# Badge_03v2-prog-2layer.net
KiCad netlist of a schematic drawn in EAGLE
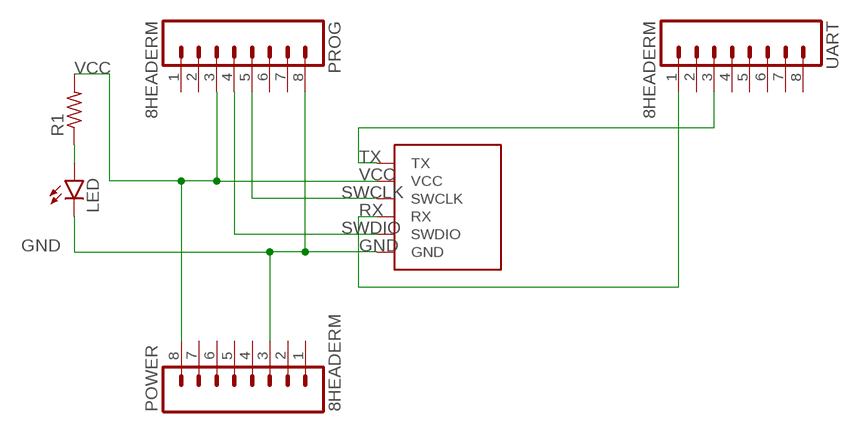
[diagram p0: schematic, sheet 1]

(export (version "E")
  (design (tool "Eeschema 10.0.6"))
  (components
    (comp (ref "J1")
      (value "PROG_CONN_6")
      (footprint "eagle-import:TH_CONN_6")
      (libsource (lib "eagle-import") (part "PROG_CONN_6"))
    )
    (comp (ref "LED")
      (value "LED")
      (footprint "eagle-import:LED-0603")
      (libsource (lib "eagle-import") (part "LED"))
    )
    (comp (ref "POWER")
      (value "8HEADERM")
      (footprint "eagle-import:1X08_ROUND")
      (libsource (lib "eagle-import") (part "8HEADERM"))
    )
    (comp (ref "PROG")
      (value "8HEADERM")
      (footprint "eagle-import:1X08_ROUND")
      (libsource (lib "eagle-import") (part "8HEADERM"))
    )
    (comp (ref "R1")
      (value "R-US_R0603")
      (footprint "eagle-import:R0603")
      (libsource (lib "eagle-import") (part "R-US_R0603"))
    )
    (comp (ref "UART")
      (value "8HEADERM")
      (footprint "eagle-import:1X08_ROUND")
      (libsource (lib "eagle-import") (part "8HEADERM"))
    )
  )
  (nets
    (net (code "1") (name "/GND") (class "Default")
      (node (ref "J1") (pin "GND") (pinfunction "GND_GND") (pintype "bidirectional"))
      (node (ref "LED") (pin "C") (pinfunction "C_C") (pintype "passive"))
      (node (ref "POWER") (pin "3") (pinfunction "3_3") (pintype "passive"))
      (node (ref "PROG") (pin "8") (pinfunction "8_8") (pintype "passive"))
    )
    (net (code "2") (name "/RX") (class "Default")
      (node (ref "J1") (pin "RX") (pinfunction "RX_RX") (pintype "bidirectional"))
      (node (ref "UART") (pin "1") (pinfunction "1_1") (pintype "passive"))
    )
    (net (code "3") (name "/SWCLK") (class "Default")
      (node (ref "J1") (pin "SWCLK") (pinfunction "SWCLK_SWCLK") (pintype "bidirectional"))
      (node (ref "PROG") (pin "5") (pinfunction "5_5") (pintype "passive"))
    )
    (net (code "4") (name "/SWDIO") (class "Default")
      (node (ref "J1") (pin "SWDIO") (pinfunction "SWDIO_SWDIO") (pintype "bidirectional"))
      (node (ref "PROG") (pin "4") (pinfunction "4_4") (pintype "passive"))
    )
    (net (code "5") (name "/TX") (class "Default")
      (node (ref "J1") (pin "TX") (pinfunction "TX_TX") (pintype "bidirectional"))
      (node (ref "UART") (pin "3") (pinfunction "3_3") (pintype "passive"))
    )
    (net (code "6") (name "/VCC") (class "Default")
      (node (ref "J1") (pin "VCC") (pinfunction "VCC_VCC") (pintype "bidirectional"))
      (node (ref "POWER") (pin "8") (pinfunction "8_8") (pintype "passive"))
      (node (ref "PROG") (pin "3") (pinfunction "3_3") (pintype "passive"))
      (node (ref "R1") (pin "2") (pinfunction "2_2") (pintype "passive"))
    )
    (net (code "7") (name "Net-(LED-PadA)") (class "Default")
      (node (ref "LED") (pin "A") (pinfunction "A_A") (pintype "passive"))
      (node (ref "R1") (pin "1") (pinfunction "1_1") (pintype "passive"))
    )
    (net (code "8") (name "unconnected-(POWER-Pad1)") (class "Default")
      (node (ref "POWER") (pin "1") (pinfunction "1_1") (pintype "passive"))
    )
    (net (code "9") (name "unconnected-(POWER-Pad2)") (class "Default")
      (node (ref "POWER") (pin "2") (pinfunction "2_2") (pintype "passive"))
    )
    (net (code "10") (name "unconnected-(POWER-Pad4)") (class "Default")
      (node (ref "POWER") (pin "4") (pinfunction "4_4") (pintype "passive"))
    )
    (net (code "11") (name "unconnected-(POWER-Pad5)") (class "Default")
      (node (ref "POWER") (pin "5") (pinfunction "5_5") (pintype "passive"))
    )
    (net (code "12") (name "unconnected-(POWER-Pad6)") (class "Default")
      (node (ref "POWER") (pin "6") (pinfunction "6_6") (pintype "passive"))
    )
    (net (code "13") (name "unconnected-(POWER-Pad7)") (class "Default")
      (node (ref "POWER") (pin "7") (pinfunction "7_7") (pintype "passive"))
    )
    (net (code "14") (name "unconnected-(PROG-Pad1)") (class "Default")
      (node (ref "PROG") (pin "1") (pinfunction "1_1") (pintype "passive"))
    )
    (net (code "15") (name "unconnected-(PROG-Pad2)") (class "Default")
      (node (ref "PROG") (pin "2") (pinfunction "2_2") (pintype "passive"))
    )
    (net (code "16") (name "unconnected-(PROG-Pad6)") (class "Default")
      (node (ref "PROG") (pin "6") (pinfunction "6_6") (pintype "passive"))
    )
    (net (code "17") (name "unconnected-(PROG-Pad7)") (class "Default")
      (node (ref "PROG") (pin "7") (pinfunction "7_7") (pintype "passive"))
    )
    (net (code "18") (name "unconnected-(UART-Pad2)") (class "Default")
      (node (ref "UART") (pin "2") (pinfunction "2_2") (pintype "passive"))
    )
    (net (code "19") (name "unconnected-(UART-Pad4)") (class "Default")
      (node (ref "UART") (pin "4") (pinfunction "4_4") (pintype "passive"))
    )
    (net (code "20") (name "unconnected-(UART-Pad5)") (class "Default")
      (node (ref "UART") (pin "5") (pinfunction "5_5") (pintype "passive"))
    )
    (net (code "21") (name "unconnected-(UART-Pad6)") (class "Default")
      (node (ref "UART") (pin "6") (pinfunction "6_6") (pintype "passive"))
    )
    (net (code "22") (name "unconnected-(UART-Pad7)") (class "Default")
      (node (ref "UART") (pin "7") (pinfunction "7_7") (pintype "passive"))
    )
    (net (code "23") (name "unconnected-(UART-Pad8)") (class "Default")
      (node (ref "UART") (pin "8") (pinfunction "8_8") (pintype "passive"))
    )
  )
)
